# sdcard.net
KiCad netlist of a schematic drawn in Altium Designer
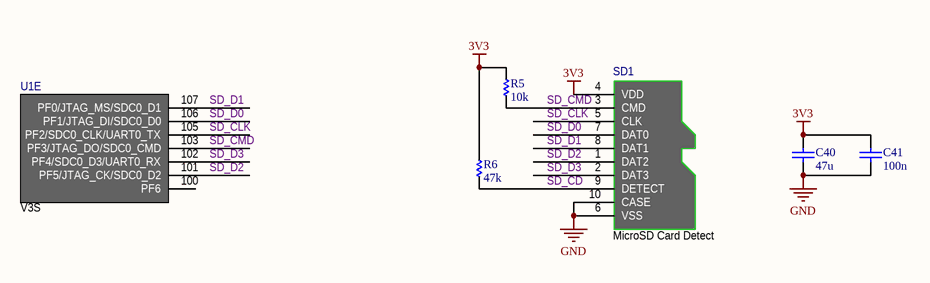
[diagram p0: sdcard.SchDoc]

(export (version "E")
  (design (tool "Eeschema 10.0.6"))
  (components
    (comp (ref "C40")
      (value "47u")
      (footprint "CAPC2012L")
      (description "Capacitor (Semiconductor SIM Model)")
      (fields (field (name "PUBLISHER") "Altium Limited"))
      (libsource (lib "Miscellaneous Devices") (part "Cap Semi"))
    )
    (comp (ref "C41")
      (value "100n")
      (footprint "CAPC1005N")
      (description "Capacitor (Semiconductor SIM Model)")
      (fields (field (name "PUBLISHER") "Altium Limited"))
      (libsource (lib "Miscellaneous Devices") (part "Cap Semi"))
    )
    (comp (ref "R5")
      (value "10k")
      (footprint "RESC1005N")
      (description "Semiconductor Resistor")
      (fields (field (name "PUBLISHER") "Altium Limited"))
      (libsource (lib "Miscellaneous Devices") (part "Res Semi"))
    )
    (comp (ref "R6")
      (value "47k")
      (footprint "RESC1005N")
      (description "Semiconductor Resistor")
      (fields (field (name "PUBLISHER") "Altium Limited"))
      (libsource (lib "Miscellaneous Devices") (part "Res Semi"))
    )
    (comp (ref "SD1")
      (value "MicroSD Card Detect")
      (footprint "47309-2851")
      (description "microSD card memory connector")
      (libsource (lib "Miscellaneous Connectors") (part "MicroSD Card Detect"))
    )
    (comp (ref "U1") (value "V3S") (footprint "V3S") (libsource (lib "Allwinner SoC") (part "V3S")))
  )
  (nets
    (net (code "1") (name "/SD_CD") (class "Default")
      (node (ref "R6") (pin "1") (pinfunction "1_1") (pintype "passive"))
      (node (ref "SD1") (pin "9") (pinfunction "DETECT_9") (pintype "power_in"))
    )
    (net (code "2") (name "/SD_CLK") (class "Default")
      (node (ref "SD1") (pin "5") (pinfunction "CLK_5") (pintype "power_in"))
      (node (ref "U1") (pin "105") (pinfunction "PF2/SDC0_CLK/UART0_TX_105") (pintype "passive"))
    )
    (net (code "3") (name "/SD_CMD") (class "Default")
      (node (ref "R5") (pin "1") (pinfunction "1_1") (pintype "passive"))
      (node (ref "SD1") (pin "3") (pinfunction "CMD_3") (pintype "power_in"))
      (node (ref "U1") (pin "103") (pinfunction "PF3/JTAG_DO/SDC0_CMD_103") (pintype "passive"))
    )
    (net (code "4") (name "/SD_D0") (class "Default")
      (node (ref "SD1") (pin "7") (pinfunction "DAT0_7") (pintype "power_in"))
      (node (ref "U1") (pin "106") (pinfunction "PF1/JTAG_DI/SDC0_D0_106") (pintype "passive"))
    )
    (net (code "5") (name "/SD_D1") (class "Default")
      (node (ref "SD1") (pin "8") (pinfunction "DAT1_8") (pintype "power_in"))
      (node (ref "U1") (pin "107") (pinfunction "PF0/JTAG_MS/SDC0_D1_107") (pintype "passive"))
    )
    (net (code "6") (name "/SD_D2") (class "Default")
      (node (ref "SD1") (pin "1") (pinfunction "DAT2_1") (pintype "power_in"))
      (node (ref "U1") (pin "101") (pinfunction "PF5/JTAG_CK/SDC0_D2_101") (pintype "passive"))
    )
    (net (code "7") (name "/SD_D3") (class "Default")
      (node (ref "SD1") (pin "2") (pinfunction "DAT3_2") (pintype "power_in"))
      (node (ref "U1") (pin "102") (pinfunction "PF4/SDC0_D3/UART0_RX_102") (pintype "passive"))
    )
    (net (code "8") (name "3V3") (class "Default")
      (node (ref "C40") (pin "2") (pinfunction "2_2") (pintype "passive"))
      (node (ref "C41") (pin "2") (pinfunction "2_2") (pintype "passive"))
      (node (ref "R5") (pin "2") (pinfunction "2_2") (pintype "passive"))
      (node (ref "R6") (pin "2") (pinfunction "2_2") (pintype "passive"))
      (node (ref "SD1") (pin "4") (pinfunction "VDD_4") (pintype "power_in"))
    )
    (net (code "9") (name "GND") (class "Default")
      (node (ref "C40") (pin "1") (pinfunction "1_1") (pintype "passive"))
      (node (ref "C41") (pin "1") (pinfunction "1_1") (pintype "passive"))
      (node (ref "SD1") (pin "10") (pinfunction "CASE_10") (pintype "power_in"))
      (node (ref "SD1") (pin "6") (pinfunction "VSS_6") (pintype "power_in"))
    )
    (net (code "10") (name "unconnected-(U1E-PF6-Pad100)") (class "Default")
      (node (ref "U1") (pin "100") (pinfunction "PF6_100") (pintype "passive"))
    )
  )
)
